# v2.net
KiCad netlist of a schematic drawn in EAGLE
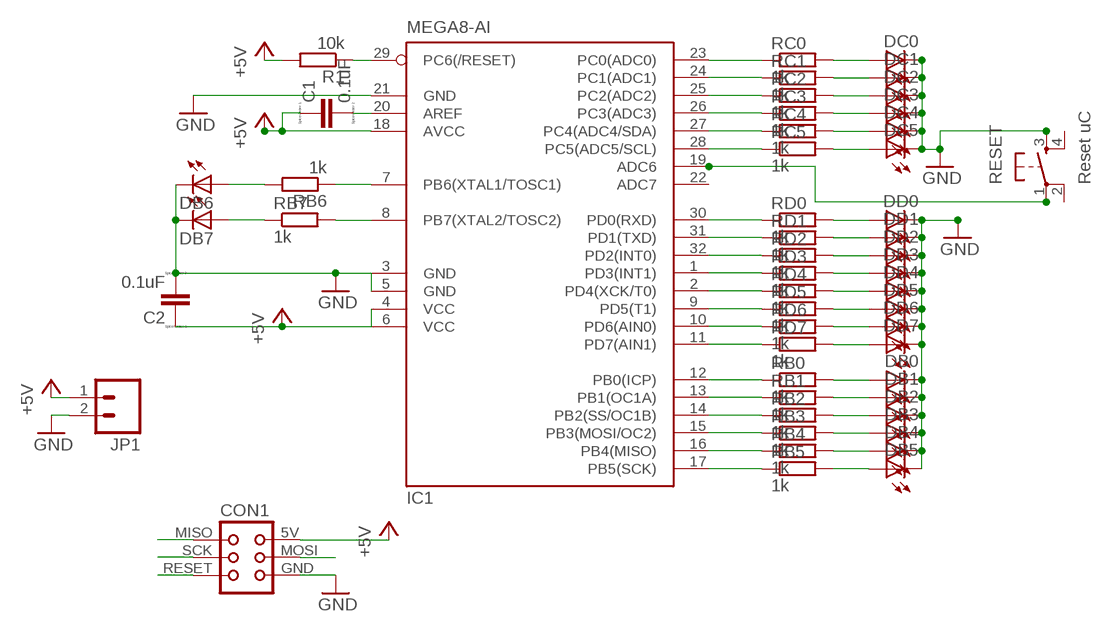
[diagram p0: schematic, sheet 1]

(export (version "E")
  (design (tool "Eeschema 10.0.6"))
  (components
    (comp (ref "C1")
      (value "0.1uF")
      (footprint "eagle-import:C0603")
      (libsource (lib "eagle-import") (part "CC0603"))
    )
    (comp (ref "C2")
      (value "0.1uF")
      (footprint "eagle-import:C0603")
      (libsource (lib "eagle-import") (part "CC0603"))
    )
    (comp (ref "CON1")
      (value "TINYISPT")
      (footprint "eagle-import:TC2030-MCP-NL")
      (libsource (lib "eagle-import") (part "TINYISPT"))
    )
    (comp (ref "DB0")
      (value "LEDCHIPLED_0603")
      (footprint "eagle-import:CHIPLED_0603")
      (libsource (lib "eagle-import") (part "LEDCHIPLED_0603"))
    )
    (comp (ref "DB1")
      (value "LEDCHIPLED_0603")
      (footprint "eagle-import:CHIPLED_0603")
      (libsource (lib "eagle-import") (part "LEDCHIPLED_0603"))
    )
    (comp (ref "DB2")
      (value "LEDCHIPLED_0603")
      (footprint "eagle-import:CHIPLED_0603")
      (libsource (lib "eagle-import") (part "LEDCHIPLED_0603"))
    )
    (comp (ref "DB3")
      (value "LEDCHIPLED_0603")
      (footprint "eagle-import:CHIPLED_0603")
      (libsource (lib "eagle-import") (part "LEDCHIPLED_0603"))
    )
    (comp (ref "DB4")
      (value "LEDCHIPLED_0603")
      (footprint "eagle-import:CHIPLED_0603")
      (libsource (lib "eagle-import") (part "LEDCHIPLED_0603"))
    )
    (comp (ref "DB5")
      (value "LEDCHIPLED_0603")
      (footprint "eagle-import:CHIPLED_0603")
      (libsource (lib "eagle-import") (part "LEDCHIPLED_0603"))
    )
    (comp (ref "DB6")
      (value "LEDCHIPLED_0603")
      (footprint "eagle-import:CHIPLED_0603")
      (libsource (lib "eagle-import") (part "LEDCHIPLED_0603"))
    )
    (comp (ref "DB7")
      (value "LEDCHIPLED_0603")
      (footprint "eagle-import:CHIPLED_0603")
      (libsource (lib "eagle-import") (part "LEDCHIPLED_0603"))
    )
    (comp (ref "DC0")
      (value "LEDCHIPLED_0603")
      (footprint "eagle-import:CHIPLED_0603")
      (libsource (lib "eagle-import") (part "LEDCHIPLED_0603"))
    )
    (comp (ref "DC1")
      (value "LEDCHIPLED_0603")
      (footprint "eagle-import:CHIPLED_0603")
      (libsource (lib "eagle-import") (part "LEDCHIPLED_0603"))
    )
    (comp (ref "DC2")
      (value "LEDCHIPLED_0603")
      (footprint "eagle-import:CHIPLED_0603")
      (libsource (lib "eagle-import") (part "LEDCHIPLED_0603"))
    )
    (comp (ref "DC3")
      (value "LEDCHIPLED_0603")
      (footprint "eagle-import:CHIPLED_0603")
      (libsource (lib "eagle-import") (part "LEDCHIPLED_0603"))
    )
    (comp (ref "DC4")
      (value "LEDCHIPLED_0603")
      (footprint "eagle-import:CHIPLED_0603")
      (libsource (lib "eagle-import") (part "LEDCHIPLED_0603"))
    )
    (comp (ref "DC5")
      (value "LEDCHIPLED_0603")
      (footprint "eagle-import:CHIPLED_0603")
      (libsource (lib "eagle-import") (part "LEDCHIPLED_0603"))
    )
    (comp (ref "DD0")
      (value "LEDCHIPLED_0603")
      (footprint "eagle-import:CHIPLED_0603")
      (libsource (lib "eagle-import") (part "LEDCHIPLED_0603"))
    )
    (comp (ref "DD1")
      (value "LEDCHIPLED_0603")
      (footprint "eagle-import:CHIPLED_0603")
      (libsource (lib "eagle-import") (part "LEDCHIPLED_0603"))
    )
    (comp (ref "DD2")
      (value "LEDCHIPLED_0603")
      (footprint "eagle-import:CHIPLED_0603")
      (libsource (lib "eagle-import") (part "LEDCHIPLED_0603"))
    )
    (comp (ref "DD3")
      (value "LEDCHIPLED_0603")
      (footprint "eagle-import:CHIPLED_0603")
      (libsource (lib "eagle-import") (part "LEDCHIPLED_0603"))
    )
    (comp (ref "DD4")
      (value "LEDCHIPLED_0603")
      (footprint "eagle-import:CHIPLED_0603")
      (libsource (lib "eagle-import") (part "LEDCHIPLED_0603"))
    )
    (comp (ref "DD5")
      (value "LEDCHIPLED_0603")
      (footprint "eagle-import:CHIPLED_0603")
      (libsource (lib "eagle-import") (part "LEDCHIPLED_0603"))
    )
    (comp (ref "DD6")
      (value "LEDCHIPLED_0603")
      (footprint "eagle-import:CHIPLED_0603")
      (libsource (lib "eagle-import") (part "LEDCHIPLED_0603"))
    )
    (comp (ref "DD7")
      (value "LEDCHIPLED_0603")
      (footprint "eagle-import:CHIPLED_0603")
      (libsource (lib "eagle-import") (part "LEDCHIPLED_0603"))
    )
    (comp (ref "IC1")
      (value "MEGA8-AI")
      (footprint "eagle-import:TQFP32-08")
      (fields (field (name "MPN") "ATMEGA8-16AU"))
      (libsource (lib "eagle-import") (part "MEGA8-AI"))
    )
    (comp (ref "JP1")
      (value "M023.5MM")
      (footprint "eagle-import:SCREWTERMINAL-3.5MM-2")
      (libsource (lib "eagle-import") (part "M023.5MM"))
    )
    (comp (ref "R1")
      (value "10k")
      (footprint "eagle-import:R0603")
      (libsource (lib "eagle-import") (part "R-EU_R0603"))
    )
    (comp (ref "RB0")
      (value "1k")
      (footprint "eagle-import:R0603")
      (libsource (lib "eagle-import") (part "R-EU_R0603"))
    )
    (comp (ref "RB1")
      (value "1k")
      (footprint "eagle-import:R0603")
      (libsource (lib "eagle-import") (part "R-EU_R0603"))
    )
    (comp (ref "RB2")
      (value "1k")
      (footprint "eagle-import:R0603")
      (libsource (lib "eagle-import") (part "R-EU_R0603"))
    )
    (comp (ref "RB3")
      (value "1k")
      (footprint "eagle-import:R0603")
      (libsource (lib "eagle-import") (part "R-EU_R0603"))
    )
    (comp (ref "RB4")
      (value "1k")
      (footprint "eagle-import:R0603")
      (libsource (lib "eagle-import") (part "R-EU_R0603"))
    )
    (comp (ref "RB5")
      (value "1k")
      (footprint "eagle-import:R0603")
      (libsource (lib "eagle-import") (part "R-EU_R0603"))
    )
    (comp (ref "RB6")
      (value "1k")
      (footprint "eagle-import:R0603")
      (libsource (lib "eagle-import") (part "R-EU_R0603"))
    )
    (comp (ref "RB7")
      (value "1k")
      (footprint "eagle-import:R0603")
      (libsource (lib "eagle-import") (part "R-EU_R0603"))
    )
    (comp (ref "RC0")
      (value "1k")
      (footprint "eagle-import:R0603")
      (libsource (lib "eagle-import") (part "R-EU_R0603"))
    )
    (comp (ref "RC1")
      (value "1k")
      (footprint "eagle-import:R0603")
      (libsource (lib "eagle-import") (part "R-EU_R0603"))
    )
    (comp (ref "RC2")
      (value "1k")
      (footprint "eagle-import:R0603")
      (libsource (lib "eagle-import") (part "R-EU_R0603"))
    )
    (comp (ref "RC3")
      (value "1k")
      (footprint "eagle-import:R0603")
      (libsource (lib "eagle-import") (part "R-EU_R0603"))
    )
    (comp (ref "RC4")
      (value "1k")
      (footprint "eagle-import:R0603")
      (libsource (lib "eagle-import") (part "R-EU_R0603"))
    )
    (comp (ref "RC5")
      (value "1k")
      (footprint "eagle-import:R0603")
      (libsource (lib "eagle-import") (part "R-EU_R0603"))
    )
    (comp (ref "RD0")
      (value "1k")
      (footprint "eagle-import:R0603")
      (libsource (lib "eagle-import") (part "R-EU_R0603"))
    )
    (comp (ref "RD1")
      (value "1k")
      (footprint "eagle-import:R0603")
      (libsource (lib "eagle-import") (part "R-EU_R0603"))
    )
    (comp (ref "RD2")
      (value "1k")
      (footprint "eagle-import:R0603")
      (libsource (lib "eagle-import") (part "R-EU_R0603"))
    )
    (comp (ref "RD3")
      (value "1k")
      (footprint "eagle-import:R0603")
      (libsource (lib "eagle-import") (part "R-EU_R0603"))
    )
    (comp (ref "RD4")
      (value "1k")
      (footprint "eagle-import:R0603")
      (libsource (lib "eagle-import") (part "R-EU_R0603"))
    )
    (comp (ref "RD5")
      (value "1k")
      (footprint "eagle-import:R0603")
      (libsource (lib "eagle-import") (part "R-EU_R0603"))
    )
    (comp (ref "RD6")
      (value "1k")
      (footprint "eagle-import:R0603")
      (libsource (lib "eagle-import") (part "R-EU_R0603"))
    )
    (comp (ref "RD7")
      (value "1k")
      (footprint "eagle-import:R0603")
      (libsource (lib "eagle-import") (part "R-EU_R0603"))
    )
    (comp (ref "RESET")
      (value "Reset uC")
      (footprint "eagle-import:TACTILE_SWITCH_SMD2")
      (libsource (lib "eagle-import") (part "TAC_SWITCH"))
    )
  )
  (nets
    (net (code "1") (name "+5V") (class "Default")
      (node (ref "C1") (pin "1") (pinfunction "1_1") (pintype "passive"))
      (node (ref "C2") (pin "1") (pinfunction "1_1") (pintype "passive"))
      (node (ref "CON1") (pin "5V") (pinfunction "VCC_5V") (pintype "passive"))
      (node (ref "IC1") (pin "18") (pinfunction "AVCC_18") (pintype "power_in"))
      (node (ref "IC1") (pin "4") (pinfunction "VCC_4") (pintype "power_in"))
      (node (ref "IC1") (pin "6") (pinfunction "VCC_6") (pintype "power_in"))
      (node (ref "JP1") (pin "1") (pinfunction "1_1") (pintype "passive"))
      (node (ref "R1") (pin "2") (pinfunction "2_2") (pintype "passive"))
    )
    (net (code "2") (name "/MISO") (class "Default")
      (node (ref "CON1") (pin "MISO") (pinfunction "MISO_MISO") (pintype "passive"))
      (node (ref "IC1") (pin "16") (pinfunction "PB4(MISO)_16") (pintype "bidirectional"))
      (node (ref "RB4") (pin "1") (pinfunction "1_1") (pintype "passive"))
    )
    (net (code "3") (name "/MOSI") (class "Default")
      (node (ref "CON1") (pin "MOSI") (pinfunction "MOSI_MOSI") (pintype "passive"))
      (node (ref "IC1") (pin "15") (pinfunction "PB3(MOSI/OC2)_15") (pintype "bidirectional"))
      (node (ref "RB3") (pin "1") (pinfunction "1_1") (pintype "passive"))
    )
    (net (code "4") (name "/RESET") (class "Default")
      (node (ref "CON1") (pin "RESET") (pinfunction "RESET_RESET") (pintype "passive"))
      (node (ref "IC1") (pin "29") (pinfunction "PC6(/RESET)_29") (pintype "bidirectional"))
      (node (ref "R1") (pin "1") (pinfunction "1_1") (pintype "passive"))
    )
    (net (code "5") (name "/SCK") (class "Default")
      (node (ref "CON1") (pin "SCK") (pinfunction "SCK_SCK") (pintype "passive"))
      (node (ref "IC1") (pin "17") (pinfunction "PB5(SCK)_17") (pintype "bidirectional"))
      (node (ref "RB5") (pin "1") (pinfunction "1_1") (pintype "passive"))
    )
    (net (code "6") (name "GND") (class "Default")
      (node (ref "C2") (pin "2") (pinfunction "2_2") (pintype "passive"))
      (node (ref "CON1") (pin "GND") (pinfunction "GND_GND") (pintype "passive"))
      (node (ref "DB0") (pin "C") (pinfunction "C_C") (pintype "passive"))
      (node (ref "DB1") (pin "C") (pinfunction "C_C") (pintype "passive"))
      (node (ref "DB2") (pin "C") (pinfunction "C_C") (pintype "passive"))
      (node (ref "DB3") (pin "C") (pinfunction "C_C") (pintype "passive"))
      (node (ref "DB4") (pin "C") (pinfunction "C_C") (pintype "passive"))
      (node (ref "DB5") (pin "C") (pinfunction "C_C") (pintype "passive"))
      (node (ref "DB6") (pin "C") (pinfunction "C_C") (pintype "passive"))
      (node (ref "DB7") (pin "C") (pinfunction "C_C") (pintype "passive"))
      (node (ref "DC0") (pin "C") (pinfunction "C_C") (pintype "passive"))
      (node (ref "DC1") (pin "C") (pinfunction "C_C") (pintype "passive"))
      (node (ref "DC2") (pin "C") (pinfunction "C_C") (pintype "passive"))
      (node (ref "DC3") (pin "C") (pinfunction "C_C") (pintype "passive"))
      (node (ref "DC4") (pin "C") (pinfunction "C_C") (pintype "passive"))
      (node (ref "DC5") (pin "C") (pinfunction "C_C") (pintype "passive"))
      (node (ref "DD0") (pin "C") (pinfunction "C_C") (pintype "passive"))
      (node (ref "DD1") (pin "C") (pinfunction "C_C") (pintype "passive"))
      (node (ref "DD2") (pin "C") (pinfunction "C_C") (pintype "passive"))
      (node (ref "DD3") (pin "C") (pinfunction "C_C") (pintype "passive"))
      (node (ref "DD4") (pin "C") (pinfunction "C_C") (pintype "passive"))
      (node (ref "DD5") (pin "C") (pinfunction "C_C") (pintype "passive"))
      (node (ref "DD6") (pin "C") (pinfunction "C_C") (pintype "passive"))
      (node (ref "DD7") (pin "C") (pinfunction "C_C") (pintype "passive"))
      (node (ref "IC1") (pin "21") (pinfunction "GND_21") (pintype "power_in"))
      (node (ref "IC1") (pin "3") (pinfunction "GND_3") (pintype "power_in"))
      (node (ref "IC1") (pin "5") (pinfunction "GND_5") (pintype "power_in"))
      (node (ref "JP1") (pin "2") (pinfunction "2_2") (pintype "passive"))
      (node (ref "RESET") (pin "3") (pinfunction "3_3") (pintype "passive"))
    )
    (net (code "7") (name "Net-(DB0-PadA)") (class "Default")
      (node (ref "DB0") (pin "A") (pinfunction "A_A") (pintype "passive"))
      (node (ref "RB0") (pin "2") (pinfunction "2_2") (pintype "passive"))
    )
    (net (code "8") (name "Net-(DB1-PadA)") (class "Default")
      (node (ref "DB1") (pin "A") (pinfunction "A_A") (pintype "passive"))
      (node (ref "RB1") (pin "2") (pinfunction "2_2") (pintype "passive"))
    )
    (net (code "9") (name "Net-(DB2-PadA)") (class "Default")
      (node (ref "DB2") (pin "A") (pinfunction "A_A") (pintype "passive"))
      (node (ref "RB2") (pin "2") (pinfunction "2_2") (pintype "passive"))
    )
    (net (code "10") (name "Net-(DB3-PadA)") (class "Default")
      (node (ref "DB3") (pin "A") (pinfunction "A_A") (pintype "passive"))
      (node (ref "RB3") (pin "2") (pinfunction "2_2") (pintype "passive"))
    )
    (net (code "11") (name "Net-(DB4-PadA)") (class "Default")
      (node (ref "DB4") (pin "A") (pinfunction "A_A") (pintype "passive"))
      (node (ref "RB4") (pin "2") (pinfunction "2_2") (pintype "passive"))
    )
    (net (code "12") (name "Net-(DB5-PadA)") (class "Default")
      (node (ref "DB5") (pin "A") (pinfunction "A_A") (pintype "passive"))
      (node (ref "RB5") (pin "2") (pinfunction "2_2") (pintype "passive"))
    )
    (net (code "13") (name "Net-(DB6-PadA)") (class "Default")
      (node (ref "DB6") (pin "A") (pinfunction "A_A") (pintype "passive"))
      (node (ref "RB6") (pin "2") (pinfunction "2_2") (pintype "passive"))
    )
    (net (code "14") (name "Net-(DB7-PadA)") (class "Default")
      (node (ref "DB7") (pin "A") (pinfunction "A_A") (pintype "passive"))
      (node (ref "RB7") (pin "1") (pinfunction "1_1") (pintype "passive"))
    )
    (net (code "15") (name "Net-(DC0-PadA)") (class "Default")
      (node (ref "DC0") (pin "A") (pinfunction "A_A") (pintype "passive"))
      (node (ref "RC0") (pin "2") (pinfunction "2_2") (pintype "passive"))
    )
    (net (code "16") (name "Net-(DC1-PadA)") (class "Default")
      (node (ref "DC1") (pin "A") (pinfunction "A_A") (pintype "passive"))
      (node (ref "RC1") (pin "2") (pinfunction "2_2") (pintype "passive"))
    )
    (net (code "17") (name "Net-(DC2-PadA)") (class "Default")
      (node (ref "DC2") (pin "A") (pinfunction "A_A") (pintype "passive"))
      (node (ref "RC2") (pin "2") (pinfunction "2_2") (pintype "passive"))
    )
    (net (code "18") (name "Net-(DC3-PadA)") (class "Default")
      (node (ref "DC3") (pin "A") (pinfunction "A_A") (pintype "passive"))
      (node (ref "RC3") (pin "2") (pinfunction "2_2") (pintype "passive"))
    )
    (net (code "19") (name "Net-(DC4-PadA)") (class "Default")
      (node (ref "DC4") (pin "A") (pinfunction "A_A") (pintype "passive"))
      (node (ref "RC4") (pin "2") (pinfunction "2_2") (pintype "passive"))
    )
    (net (code "20") (name "Net-(DC5-PadA)") (class "Default")
      (node (ref "DC5") (pin "A") (pinfunction "A_A") (pintype "passive"))
      (node (ref "RC5") (pin "2") (pinfunction "2_2") (pintype "passive"))
    )
    (net (code "21") (name "Net-(DD0-PadA)") (class "Default")
      (node (ref "DD0") (pin "A") (pinfunction "A_A") (pintype "passive"))
      (node (ref "RD0") (pin "2") (pinfunction "2_2") (pintype "passive"))
    )
    (net (code "22") (name "Net-(DD1-PadA)") (class "Default")
      (node (ref "DD1") (pin "A") (pinfunction "A_A") (pintype "passive"))
      (node (ref "RD1") (pin "2") (pinfunction "2_2") (pintype "passive"))
    )
    (net (code "23") (name "Net-(DD2-PadA)") (class "Default")
      (node (ref "DD2") (pin "A") (pinfunction "A_A") (pintype "passive"))
      (node (ref "RD2") (pin "2") (pinfunction "2_2") (pintype "passive"))
    )
    (net (code "24") (name "Net-(DD3-PadA)") (class "Default")
      (node (ref "DD3") (pin "A") (pinfunction "A_A") (pintype "passive"))
      (node (ref "RD3") (pin "2") (pinfunction "2_2") (pintype "passive"))
    )
    (net (code "25") (name "Net-(DD4-PadA)") (class "Default")
      (node (ref "DD4") (pin "A") (pinfunction "A_A") (pintype "passive"))
      (node (ref "RD4") (pin "2") (pinfunction "2_2") (pintype "passive"))
    )
    (net (code "26") (name "Net-(DD5-PadA)") (class "Default")
      (node (ref "DD5") (pin "A") (pinfunction "A_A") (pintype "passive"))
      (node (ref "RD5") (pin "2") (pinfunction "2_2") (pintype "passive"))
    )
    (net (code "27") (name "Net-(DD6-PadA)") (class "Default")
      (node (ref "DD6") (pin "A") (pinfunction "A_A") (pintype "passive"))
      (node (ref "RD6") (pin "2") (pinfunction "2_2") (pintype "passive"))
    )
    (net (code "28") (name "Net-(DD7-PadA)") (class "Default")
      (node (ref "DD7") (pin "A") (pinfunction "A_A") (pintype "passive"))
      (node (ref "RD7") (pin "2") (pinfunction "2_2") (pintype "passive"))
    )
    (net (code "29") (name "Net-(IC1-ADC6)") (class "Default")
      (node (ref "IC1") (pin "19") (pinfunction "ADC6_19") (pintype "bidirectional"))
      (node (ref "RESET") (pin "1") (pinfunction "1_1") (pintype "passive"))
    )
    (net (code "30") (name "Net-(IC1-AREF)") (class "Default")
      (node (ref "C1") (pin "2") (pinfunction "2_2") (pintype "passive"))
      (node (ref "IC1") (pin "20") (pinfunction "AREF_20") (pintype "passive"))
    )
    (net (code "31") (name "Net-(IC1-PB0(ICP))") (class "Default")
      (node (ref "IC1") (pin "12") (pinfunction "PB0(ICP)_12") (pintype "bidirectional"))
      (node (ref "RB0") (pin "1") (pinfunction "1_1") (pintype "passive"))
    )
    (net (code "32") (name "Net-(IC1-PB1(OC1A))") (class "Default")
      (node (ref "IC1") (pin "13") (pinfunction "PB1(OC1A)_13") (pintype "bidirectional"))
      (node (ref "RB1") (pin "1") (pinfunction "1_1") (pintype "passive"))
    )
    (net (code "33") (name "Net-(IC1-PB2(SS{slash}OC1B))") (class "Default")
      (node (ref "IC1") (pin "14") (pinfunction "PB2(SS/OC1B)_14") (pintype "bidirectional"))
      (node (ref "RB2") (pin "1") (pinfunction "1_1") (pintype "passive"))
    )
    (net (code "34") (name "Net-(IC1-PB6(XTAL1{slash}TOSC1))") (class "Default")
      (node (ref "IC1") (pin "7") (pinfunction "PB6(XTAL1/TOSC1)_7") (pintype "bidirectional"))
      (node (ref "RB6") (pin "1") (pinfunction "1_1") (pintype "passive"))
    )
    (net (code "35") (name "Net-(IC1-PB7(XTAL2{slash}TOSC2))") (class "Default")
      (node (ref "IC1") (pin "8") (pinfunction "PB7(XTAL2/TOSC2)_8") (pintype "bidirectional"))
      (node (ref "RB7") (pin "2") (pinfunction "2_2") (pintype "passive"))
    )
    (net (code "36") (name "Net-(IC1-PC0(ADC0))") (class "Default")
      (node (ref "IC1") (pin "23") (pinfunction "PC0(ADC0)_23") (pintype "bidirectional"))
      (node (ref "RC0") (pin "1") (pinfunction "1_1") (pintype "passive"))
    )
    (net (code "37") (name "Net-(IC1-PC1(ADC1))") (class "Default")
      (node (ref "IC1") (pin "24") (pinfunction "PC1(ADC1)_24") (pintype "bidirectional"))
      (node (ref "RC1") (pin "1") (pinfunction "1_1") (pintype "passive"))
    )
    (net (code "38") (name "Net-(IC1-PC2(ADC2))") (class "Default")
      (node (ref "IC1") (pin "25") (pinfunction "PC2(ADC2)_25") (pintype "bidirectional"))
      (node (ref "RC2") (pin "1") (pinfunction "1_1") (pintype "passive"))
    )
    (net (code "39") (name "Net-(IC1-PC3(ADC3))") (class "Default")
      (node (ref "IC1") (pin "26") (pinfunction "PC3(ADC3)_26") (pintype "bidirectional"))
      (node (ref "RC3") (pin "1") (pinfunction "1_1") (pintype "passive"))
    )
    (net (code "40") (name "Net-(IC1-PC4(ADC4{slash}SDA))") (class "Default")
      (node (ref "IC1") (pin "27") (pinfunction "PC4(ADC4/SDA)_27") (pintype "bidirectional"))
      (node (ref "RC4") (pin "1") (pinfunction "1_1") (pintype "passive"))
    )
    (net (code "41") (name "Net-(IC1-PC5(ADC5{slash}SCL))") (class "Default")
      (node (ref "IC1") (pin "28") (pinfunction "PC5(ADC5/SCL)_28") (pintype "bidirectional"))
      (node (ref "RC5") (pin "1") (pinfunction "1_1") (pintype "passive"))
    )
    (net (code "42") (name "Net-(IC1-PD0(RXD))") (class "Default")
      (node (ref "IC1") (pin "30") (pinfunction "PD0(RXD)_30") (pintype "bidirectional"))
      (node (ref "RD0") (pin "1") (pinfunction "1_1") (pintype "passive"))
    )
    (net (code "43") (name "Net-(IC1-PD1(TXD))") (class "Default")
      (node (ref "IC1") (pin "31") (pinfunction "PD1(TXD)_31") (pintype "bidirectional"))
      (node (ref "RD1") (pin "1") (pinfunction "1_1") (pintype "passive"))
    )
    (net (code "44") (name "Net-(IC1-PD2(INT0))") (class "Default")
      (node (ref "IC1") (pin "32") (pinfunction "PD2(INT0)_32") (pintype "bidirectional"))
      (node (ref "RD2") (pin "1") (pinfunction "1_1") (pintype "passive"))
    )
    (net (code "45") (name "Net-(IC1-PD3(INT1))") (class "Default")
      (node (ref "IC1") (pin "1") (pinfunction "PD3(INT1)_1") (pintype "bidirectional"))
      (node (ref "RD3") (pin "1") (pinfunction "1_1") (pintype "passive"))
    )
    (net (code "46") (name "Net-(IC1-PD4(XCK{slash}T0))") (class "Default")
      (node (ref "IC1") (pin "2") (pinfunction "PD4(XCK/T0)_2") (pintype "bidirectional"))
      (node (ref "RD4") (pin "1") (pinfunction "1_1") (pintype "passive"))
    )
    (net (code "47") (name "Net-(IC1-PD5(T1))") (class "Default")
      (node (ref "IC1") (pin "9") (pinfunction "PD5(T1)_9") (pintype "bidirectional"))
      (node (ref "RD5") (pin "1") (pinfunction "1_1") (pintype "passive"))
    )
    (net (code "48") (name "Net-(IC1-PD6(AIN0))") (class "Default")
      (node (ref "IC1") (pin "10") (pinfunction "PD6(AIN0)_10") (pintype "bidirectional"))
      (node (ref "RD6") (pin "1") (pinfunction "1_1") (pintype "passive"))
    )
    (net (code "49") (name "Net-(IC1-PD7(AIN1))") (class "Default")
      (node (ref "IC1") (pin "11") (pinfunction "PD7(AIN1)_11") (pintype "bidirectional"))
      (node (ref "RD7") (pin "1") (pinfunction "1_1") (pintype "passive"))
    )
    (net (code "50") (name "unconnected-(IC1-ADC7-Pad22)") (class "Default")
      (node (ref "IC1") (pin "22") (pinfunction "ADC7_22") (pintype "bidirectional"))
    )
    (net (code "51") (name "unconnected-(RESET-Pad2)") (class "Default")
      (node (ref "RESET") (pin "2") (pinfunction "2_2") (pintype "passive"))
    )
    (net (code "52") (name "unconnected-(RESET-Pad4)") (class "Default")
      (node (ref "RESET") (pin "4") (pinfunction "4_4") (pintype "passive"))
    )
  )
)
